# Metlino_QUAD_BUCK.net
KiCad netlist of a schematic drawn in Altium Designer
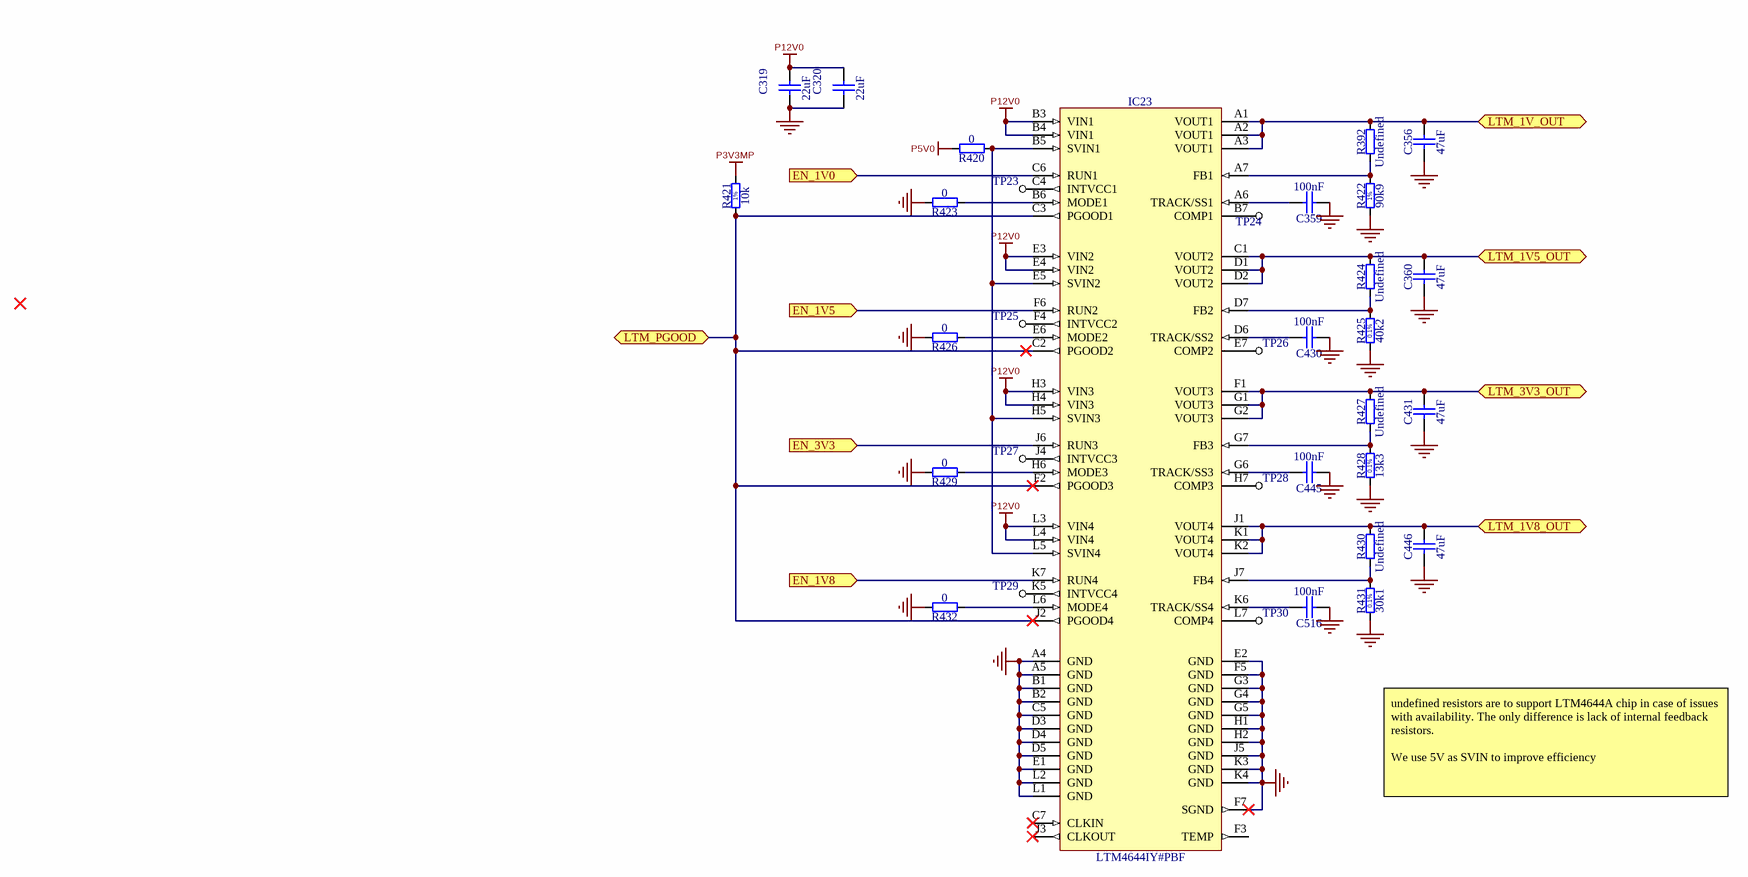
[diagram p0: Metlino_QUAD_BUCK.SchDoc]

(export (version "E")
  (design (tool "Eeschema 10.0.6"))
  (components
    (comp (ref "C319")
      (value "22uF")
      (footprint "CAPC2012X135N")
      (description "Non-polarised capacitor")
      (fields
        (field (name "MANUFACTURER PART NUMBER") "CC0805_22UF_16V_10%_X5R")
        (field (name "MANUFACTURER") "GENERIC")
        (field (name "AUTHOR") "CERN DEM JLC")
      )
      (libsource (lib "Capacitors") (part "Capacitor - non polarized"))
    )
    (comp (ref "C320")
      (value "22uF")
      (footprint "CAPC2012X135N")
      (description "Non-polarised capacitor")
      (fields
        (field (name "MANUFACTURER PART NUMBER") "CC0805_22UF_16V_10%_X5R")
        (field (name "MANUFACTURER") "GENERIC")
        (field (name "AUTHOR") "CERN DEM JLC")
      )
      (libsource (lib "Capacitors") (part "Capacitor - non polarized"))
    )
    (comp (ref "C356")
      (value "47uF")
      (footprint "CAPC2012X140N")
      (description "Non-polarised capacitor")
      (fields
        (field (name "MANUFACTURER PART NUMBER") "CC0805_47UF_6.3V_20%_X5R")
        (field (name "MANUFACTURER") "GENERIC")
        (field (name "AUTHOR") "CERN DEM JLC")
      )
      (libsource (lib "Capacitors") (part "Capacitor - non polarized"))
    )
    (comp (ref "C359")
      (value "100nF")
      (footprint "CAPC1005X55N")
      (description "Non-polarised capacitor")
      (fields
        (field (name "PART NUMBER") "CC0402_100NF_16V_10%_X5R")
        (field (name "VOLTAGE") "16V")
        (field (name "AUTHOR") "CERN DEM JLC")
      )
      (libsource (lib "Capacitors") (part "Capacitor - non polarized"))
    )
    (comp (ref "C360")
      (value "47uF")
      (footprint "CAPC2012X140N")
      (description "Non-polarised capacitor")
      (fields
        (field (name "MANUFACTURER PART NUMBER") "CC0805_47UF_6.3V_20%_X5R")
        (field (name "MANUFACTURER") "GENERIC")
        (field (name "AUTHOR") "CERN DEM JLC")
      )
      (libsource (lib "Capacitors") (part "Capacitor - non polarized"))
    )
    (comp (ref "C430")
      (value "100nF")
      (footprint "CAPC1005X55N")
      (description "Non-polarised capacitor")
      (fields
        (field (name "PART NUMBER") "CC0402_100NF_16V_10%_X5R")
        (field (name "VOLTAGE") "16V")
        (field (name "AUTHOR") "CERN DEM JLC")
      )
      (libsource (lib "Capacitors") (part "Capacitor - non polarized"))
    )
    (comp (ref "C431")
      (value "47uF")
      (footprint "CAPC2012X140N")
      (description "Non-polarised capacitor")
      (fields
        (field (name "MANUFACTURER PART NUMBER") "CC0805_47UF_6.3V_20%_X5R")
        (field (name "MANUFACTURER") "GENERIC")
        (field (name "AUTHOR") "CERN DEM JLC")
      )
      (libsource (lib "Capacitors") (part "Capacitor - non polarized"))
    )
    (comp (ref "C445")
      (value "100nF")
      (footprint "CAPC1005X55N")
      (description "Non-polarised capacitor")
      (fields
        (field (name "PART NUMBER") "CC0402_100NF_16V_10%_X5R")
        (field (name "VOLTAGE") "16V")
        (field (name "AUTHOR") "CERN DEM JLC")
      )
      (libsource (lib "Capacitors") (part "Capacitor - non polarized"))
    )
    (comp (ref "C446")
      (value "47uF")
      (footprint "CAPC2012X140N")
      (description "Non-polarised capacitor")
      (fields
        (field (name "MANUFACTURER PART NUMBER") "CC0805_47UF_6.3V_20%_X5R")
        (field (name "MANUFACTURER") "GENERIC")
        (field (name "AUTHOR") "CERN DEM JLC")
      )
      (libsource (lib "Capacitors") (part "Capacitor - non polarized"))
    )
    (comp (ref "C516")
      (value "100nF")
      (footprint "CAPC1005X55N")
      (description "Non-polarised capacitor")
      (fields
        (field (name "PART NUMBER") "CC0402_100NF_16V_10%_X5R")
        (field (name "VOLTAGE") "16V")
        (field (name "AUTHOR") "CERN DEM JLC")
      )
      (libsource (lib "Capacitors") (part "Capacitor - non polarized"))
    )
    (comp (ref "IC23")
      (value "LTM4644IY#PBF")
      (footprint "BGA77C127P7X11_900X1500X521")
      (description "Quad DC/DC µModule Regulator with Configurable 4A Output Array")
      (fields (field (name "MANUFACTURER") "LINEAR TECHNOLOGY") (field (name "AUTHOR") "CERN DEM JLC"))
      (libsource (lib "ICs And Semiconductors") (part "LTM4644"))
    )
    (comp (ref "R392")
      (value "Undefined")
      (footprint "RESC1608X55N")
      (description "Resistor")
      (fields (field (name "PART NUMBER") "R0603_NO-VALUE") (field (name "AUTHOR") "CERN DEM JLC"))
      (libsource (lib "Resistors") (part "Resistor"))
    )
    (comp (ref "R420")
      (value "0")
      (footprint "RESC1005X40N")
      (description "Resistor")
      (fields
        (field (name "MANUFACTURER PART NUMBER") "R0402_0R_JUMPER")
        (field (name "MANUFACTURER") "GENERIC")
        (field (name "AUTHOR") "CERN DEM JLC")
      )
      (libsource (lib "Resistors") (part "Resistor"))
    )
    (comp (ref "R421")
      (value "10k")
      (footprint "RESC1005X40N")
      (description "Resistor - 1%")
      (fields
        (field (name "MANUFACTURER PART NUMBER") "R0402_10K_1%_0.0625W_100PPM")
        (field (name "MANUFACTURER") "GENERIC")
        (field (name "AUTHOR") "CERN DEM JLC")
      )
      (libsource (lib "Resistors") (part "Resistor - 1%"))
    )
    (comp (ref "R422")
      (value "90k9")
      (footprint "RESC1608X55N")
      (description "Resistor - 1%")
      (fields
        (field (name "PART NUMBER") "R0603_90K9_1%_0.1W_100PPM")
        (field (name "POWER") "0.1W")
        (field (name "AUTHOR") "CERN DEM JLC")
      )
      (libsource (lib "Resistors") (part "Resistor - 1%"))
    )
    (comp (ref "R423")
      (value "0")
      (footprint "RESC1005X40N")
      (description "Resistor")
      (fields
        (field (name "MANUFACTURER PART NUMBER") "R0402_0R_JUMPER")
        (field (name "MANUFACTURER") "GENERIC")
        (field (name "AUTHOR") "CERN DEM JLC")
      )
      (libsource (lib "Resistors") (part "Resistor"))
    )
    (comp (ref "R424")
      (value "Undefined")
      (footprint "RESC1608X55N")
      (description "Resistor")
      (fields (field (name "PART NUMBER") "R0603_NO-VALUE") (field (name "AUTHOR") "CERN DEM JLC"))
      (libsource (lib "Resistors") (part "Resistor"))
    )
    (comp (ref "R425")
      (value "40k2")
      (footprint "RESC1608X55N")
      (description "Resistor - 0.1%")
      (fields
        (field (name "PART NUMBER") "R0603_40K2_0.1%_0.063W_10PPM")
        (field (name "POWER") "0.063W")
        (field (name "AUTHOR") "CERN DEM JLC")
      )
      (libsource (lib "Resistors") (part "Resistor - 0.1%"))
    )
    (comp (ref "R426")
      (value "0")
      (footprint "RESC1005X40N")
      (description "Resistor")
      (fields
        (field (name "MANUFACTURER PART NUMBER") "R0402_0R_JUMPER")
        (field (name "MANUFACTURER") "GENERIC")
        (field (name "AUTHOR") "CERN DEM JLC")
      )
      (libsource (lib "Resistors") (part "Resistor"))
    )
    (comp (ref "R427")
      (value "Undefined")
      (footprint "RESC1608X55N")
      (description "Resistor")
      (fields (field (name "PART NUMBER") "R0603_NO-VALUE") (field (name "AUTHOR") "CERN DEM JLC"))
      (libsource (lib "Resistors") (part "Resistor"))
    )
    (comp (ref "R428")
      (value "13k3")
      (footprint "RESC1608X55N")
      (description "Resistor - 0.1%")
      (fields
        (field (name "PART NUMBER") "R0603_13K3_0.1%_0.063W_10PPM")
        (field (name "POWER") "0.063W")
        (field (name "AUTHOR") "CERN DEM JLC")
      )
      (libsource (lib "Resistors") (part "Resistor - 0.1%"))
    )
    (comp (ref "R429")
      (value "0")
      (footprint "RESC1005X40N")
      (description "Resistor")
      (fields
        (field (name "MANUFACTURER PART NUMBER") "R0402_0R_JUMPER")
        (field (name "MANUFACTURER") "GENERIC")
        (field (name "AUTHOR") "CERN DEM JLC")
      )
      (libsource (lib "Resistors") (part "Resistor"))
    )
    (comp (ref "R430")
      (value "Undefined")
      (footprint "RESC1608X55N")
      (description "Resistor")
      (fields (field (name "PART NUMBER") "R0603_NO-VALUE") (field (name "AUTHOR") "CERN DEM JLC"))
      (libsource (lib "Resistors") (part "Resistor"))
    )
    (comp (ref "R431")
      (value "30k1")
      (footprint "RESC1608X55N")
      (description "Resistor - 0.1%")
      (fields
        (field (name "PART NUMBER") "R0603_30K1_0.1%_0.063W_10PPM")
        (field (name "POWER") "0.063W")
        (field (name "AUTHOR") "CERN DEM JLC")
      )
      (libsource (lib "Resistors") (part "Resistor - 0.1%"))
    )
    (comp (ref "R432")
      (value "0")
      (footprint "RESC1005X40N")
      (description "Resistor")
      (fields
        (field (name "MANUFACTURER PART NUMBER") "R0402_0R_JUMPER")
        (field (name "MANUFACTURER") "GENERIC")
        (field (name "AUTHOR") "CERN DEM JLC")
      )
      (libsource (lib "Resistors") (part "Resistor"))
    )
    (comp (ref "TP23")
      (value "TP")
      (footprint "TP")
      (description "Testpoint")
      (libsource (lib "LIBRARY_SCH") (part "TP"))
    )
    (comp (ref "TP24")
      (value "TP")
      (footprint "TP")
      (description "Testpoint")
      (libsource (lib "LIBRARY_SCH") (part "TP"))
    )
    (comp (ref "TP25")
      (value "TP")
      (footprint "TP")
      (description "Testpoint")
      (libsource (lib "LIBRARY_SCH") (part "TP"))
    )
    (comp (ref "TP26")
      (value "TP")
      (footprint "TP")
      (description "Testpoint")
      (libsource (lib "LIBRARY_SCH") (part "TP"))
    )
    (comp (ref "TP27")
      (value "TP")
      (footprint "TP")
      (description "Testpoint")
      (libsource (lib "LIBRARY_SCH") (part "TP"))
    )
    (comp (ref "TP28")
      (value "TP")
      (footprint "TP")
      (description "Testpoint")
      (libsource (lib "LIBRARY_SCH") (part "TP"))
    )
    (comp (ref "TP29")
      (value "TP")
      (footprint "TP")
      (description "Testpoint")
      (libsource (lib "LIBRARY_SCH") (part "TP"))
    )
    (comp (ref "TP30")
      (value "TP")
      (footprint "TP")
      (description "Testpoint")
      (libsource (lib "LIBRARY_SCH") (part "TP"))
    )
  )
  (nets
    (net (code "1") (name "/EN_1V0") (class "Default")
      (node (ref "IC23") (pin "C6") (pinfunction "RUN1_C6") (pintype "input"))
    )
    (net (code "2") (name "/EN_1V5") (class "Default")
      (node (ref "IC23") (pin "F6") (pinfunction "RUN2_F6") (pintype "input"))
    )
    (net (code "3") (name "/EN_1V8") (class "Default")
      (node (ref "IC23") (pin "K7") (pinfunction "RUN4_K7") (pintype "input"))
    )
    (net (code "4") (name "/EN_3V3") (class "Default")
      (node (ref "IC23") (pin "J6") (pinfunction "RUN3_J6") (pintype "input"))
    )
    (net (code "5") (name "/LTM_1V5_OUT") (class "Default")
      (node (ref "C360") (pin "2") (pinfunction "2_2") (pintype "passive"))
      (node (ref "IC23") (pin "C1") (pinfunction "VOUT2_C1") (pintype "power_in"))
      (node (ref "IC23") (pin "D1") (pinfunction "VOUT2_D1") (pintype "power_in"))
      (node (ref "IC23") (pin "D2") (pinfunction "VOUT2_D2") (pintype "power_in"))
      (node (ref "R424") (pin "2") (pinfunction "2_2") (pintype "passive"))
    )
    (net (code "6") (name "/LTM_1V8_OUT") (class "Default")
      (node (ref "C446") (pin "2") (pinfunction "2_2") (pintype "passive"))
      (node (ref "IC23") (pin "J1") (pinfunction "VOUT4_J1") (pintype "power_in"))
      (node (ref "IC23") (pin "K1") (pinfunction "VOUT4_K1") (pintype "power_in"))
      (node (ref "IC23") (pin "K2") (pinfunction "VOUT4_K2") (pintype "power_in"))
      (node (ref "R430") (pin "2") (pinfunction "2_2") (pintype "passive"))
    )
    (net (code "7") (name "/LTM_1V_OUT") (class "Default")
      (node (ref "C356") (pin "2") (pinfunction "2_2") (pintype "passive"))
      (node (ref "IC23") (pin "A1") (pinfunction "VOUT1_A1") (pintype "power_in"))
      (node (ref "IC23") (pin "A2") (pinfunction "VOUT1_A2") (pintype "power_in"))
      (node (ref "IC23") (pin "A3") (pinfunction "VOUT1_A3") (pintype "power_in"))
      (node (ref "R392") (pin "2") (pinfunction "2_2") (pintype "passive"))
    )
    (net (code "8") (name "/LTM_3V3_OUT") (class "Default")
      (node (ref "C431") (pin "2") (pinfunction "2_2") (pintype "passive"))
      (node (ref "IC23") (pin "F1") (pinfunction "VOUT3_F1") (pintype "power_in"))
      (node (ref "IC23") (pin "G1") (pinfunction "VOUT3_G1") (pintype "power_in"))
      (node (ref "IC23") (pin "G2") (pinfunction "VOUT3_G2") (pintype "power_in"))
      (node (ref "R427") (pin "2") (pinfunction "2_2") (pintype "passive"))
    )
    (net (code "9") (name "/LTM_PGOOD") (class "Default")
      (node (ref "IC23") (pin "C2") (pinfunction "PGOOD2_C2") (pintype "output"))
      (node (ref "IC23") (pin "C3") (pinfunction "PGOOD1_C3") (pintype "output"))
      (node (ref "IC23") (pin "F2") (pinfunction "PGOOD3_F2") (pintype "output"))
      (node (ref "IC23") (pin "J2") (pinfunction "PGOOD4_J2") (pintype "output"))
      (node (ref "R421") (pin "1") (pinfunction "1_1") (pintype "passive"))
    )
    (net (code "10") (name "GND") (class "Default")
      (node (ref "C319") (pin "1") (pinfunction "1_1") (pintype "passive"))
      (node (ref "C320") (pin "1") (pinfunction "1_1") (pintype "passive"))
      (node (ref "C356") (pin "1") (pinfunction "1_1") (pintype "passive"))
      (node (ref "C359") (pin "1") (pinfunction "1_1") (pintype "passive"))
      (node (ref "C360") (pin "1") (pinfunction "1_1") (pintype "passive"))
      (node (ref "C430") (pin "1") (pinfunction "1_1") (pintype "passive"))
      (node (ref "C431") (pin "1") (pinfunction "1_1") (pintype "passive"))
      (node (ref "C445") (pin "1") (pinfunction "1_1") (pintype "passive"))
      (node (ref "C446") (pin "1") (pinfunction "1_1") (pintype "passive"))
      (node (ref "C516") (pin "1") (pinfunction "1_1") (pintype "passive"))
      (node (ref "IC23") (pin "A4") (pinfunction "GND_A4") (pintype "power_in"))
      (node (ref "IC23") (pin "A5") (pinfunction "GND_A5") (pintype "power_in"))
      (node (ref "IC23") (pin "B1") (pinfunction "GND_B1") (pintype "power_in"))
      (node (ref "IC23") (pin "B2") (pinfunction "GND_B2") (pintype "power_in"))
      (node (ref "IC23") (pin "C5") (pinfunction "GND_C5") (pintype "power_in"))
      (node (ref "IC23") (pin "D3") (pinfunction "GND_D3") (pintype "power_in"))
      (node (ref "IC23") (pin "D4") (pinfunction "GND_D4") (pintype "power_in"))
      (node (ref "IC23") (pin "D5") (pinfunction "GND_D5") (pintype "power_in"))
      (node (ref "IC23") (pin "E1") (pinfunction "GND_E1") (pintype "power_in"))
      (node (ref "IC23") (pin "E2") (pinfunction "GND_E2") (pintype "power_in"))
      (node (ref "IC23") (pin "F5") (pinfunction "GND_F5") (pintype "power_in"))
      (node (ref "IC23") (pin "F7") (pinfunction "SGND_F7") (pintype "output"))
      (node (ref "IC23") (pin "G3") (pinfunction "GND_G3") (pintype "power_in"))
      (node (ref "IC23") (pin "G4") (pinfunction "GND_G4") (pintype "power_in"))
      (node (ref "IC23") (pin "G5") (pinfunction "GND_G5") (pintype "power_in"))
      (node (ref "IC23") (pin "H1") (pinfunction "GND_H1") (pintype "power_in"))
      (node (ref "IC23") (pin "H2") (pinfunction "GND_H2") (pintype "power_in"))
      (node (ref "IC23") (pin "J5") (pinfunction "GND_J5") (pintype "power_in"))
      (node (ref "IC23") (pin "K3") (pinfunction "GND_K3") (pintype "power_in"))
      (node (ref "IC23") (pin "K4") (pinfunction "GND_K4") (pintype "power_in"))
      (node (ref "IC23") (pin "L1") (pinfunction "GND_L1") (pintype "power_in"))
      (node (ref "IC23") (pin "L2") (pinfunction "GND_L2") (pintype "power_in"))
      (node (ref "R422") (pin "1") (pinfunction "1_1") (pintype "passive"))
      (node (ref "R423") (pin "2") (pinfunction "2_2") (pintype "passive"))
      (node (ref "R425") (pin "1") (pinfunction "1_1") (pintype "passive"))
      (node (ref "R426") (pin "2") (pinfunction "2_2") (pintype "passive"))
      (node (ref "R428") (pin "1") (pinfunction "1_1") (pintype "passive"))
      (node (ref "R429") (pin "2") (pinfunction "2_2") (pintype "passive"))
      (node (ref "R431") (pin "1") (pinfunction "1_1") (pintype "passive"))
      (node (ref "R432") (pin "2") (pinfunction "2_2") (pintype "passive"))
    )
    (net (code "11") (name "Net-(IC23-COMP1)") (class "Default")
      (node (ref "IC23") (pin "B7") (pinfunction "COMP1_B7") (pintype "passive"))
      (node (ref "TP24") (pin "1") (pintype "passive"))
    )
    (net (code "12") (name "Net-(IC23-COMP2)") (class "Default")
      (node (ref "IC23") (pin "E7") (pinfunction "COMP2_E7") (pintype "passive"))
      (node (ref "TP26") (pin "1") (pintype "passive"))
    )
    (net (code "13") (name "Net-(IC23-COMP3)") (class "Default")
      (node (ref "IC23") (pin "H7") (pinfunction "COMP3_H7") (pintype "passive"))
      (node (ref "TP28") (pin "1") (pintype "passive"))
    )
    (net (code "14") (name "Net-(IC23-COMP4)") (class "Default")
      (node (ref "IC23") (pin "L7") (pinfunction "COMP4_L7") (pintype "passive"))
      (node (ref "TP30") (pin "1") (pintype "passive"))
    )
    (net (code "15") (name "Net-(IC23-FB1)") (class "Default")
      (node (ref "IC23") (pin "A7") (pinfunction "FB1_A7") (pintype "input"))
      (node (ref "R392") (pin "1") (pinfunction "1_1") (pintype "passive"))
      (node (ref "R422") (pin "2") (pinfunction "2_2") (pintype "passive"))
    )
    (net (code "16") (name "Net-(IC23-FB2)") (class "Default")
      (node (ref "IC23") (pin "D7") (pinfunction "FB2_D7") (pintype "input"))
      (node (ref "R424") (pin "1") (pinfunction "1_1") (pintype "passive"))
      (node (ref "R425") (pin "2") (pinfunction "2_2") (pintype "passive"))
    )
    (net (code "17") (name "Net-(IC23-FB3)") (class "Default")
      (node (ref "IC23") (pin "G7") (pinfunction "FB3_G7") (pintype "input"))
      (node (ref "R427") (pin "1") (pinfunction "1_1") (pintype "passive"))
      (node (ref "R428") (pin "2") (pinfunction "2_2") (pintype "passive"))
    )
    (net (code "18") (name "Net-(IC23-FB4)") (class "Default")
      (node (ref "IC23") (pin "J7") (pinfunction "FB4_J7") (pintype "input"))
      (node (ref "R430") (pin "1") (pinfunction "1_1") (pintype "passive"))
      (node (ref "R431") (pin "2") (pinfunction "2_2") (pintype "passive"))
    )
    (net (code "19") (name "Net-(IC23-INTVCC1)") (class "Default")
      (node (ref "IC23") (pin "C4") (pinfunction "INTVCC1_C4") (pintype "output"))
      (node (ref "TP23") (pin "1") (pintype "passive"))
    )
    (net (code "20") (name "Net-(IC23-INTVCC2)") (class "Default")
      (node (ref "IC23") (pin "F4") (pinfunction "INTVCC2_F4") (pintype "output"))
      (node (ref "TP25") (pin "1") (pintype "passive"))
    )
    (net (code "21") (name "Net-(IC23-INTVCC3)") (class "Default")
      (node (ref "IC23") (pin "J4") (pinfunction "INTVCC3_J4") (pintype "output"))
      (node (ref "TP27") (pin "1") (pintype "passive"))
    )
    (net (code "22") (name "Net-(IC23-INTVCC4)") (class "Default")
      (node (ref "IC23") (pin "K5") (pinfunction "INTVCC4_K5") (pintype "output"))
      (node (ref "TP29") (pin "1") (pintype "passive"))
    )
    (net (code "23") (name "Net-(IC23-MODE1)") (class "Default")
      (node (ref "IC23") (pin "B6") (pinfunction "MODE1_B6") (pintype "input"))
      (node (ref "R423") (pin "1") (pinfunction "1_1") (pintype "passive"))
    )
    (net (code "24") (name "Net-(IC23-MODE2)") (class "Default")
      (node (ref "IC23") (pin "E6") (pinfunction "MODE2_E6") (pintype "input"))
      (node (ref "R426") (pin "1") (pinfunction "1_1") (pintype "passive"))
    )
    (net (code "25") (name "Net-(IC23-MODE3)") (class "Default")
      (node (ref "IC23") (pin "H6") (pinfunction "MODE3_H6") (pintype "input"))
      (node (ref "R429") (pin "1") (pinfunction "1_1") (pintype "passive"))
    )
    (net (code "26") (name "Net-(IC23-MODE4)") (class "Default")
      (node (ref "IC23") (pin "L6") (pinfunction "MODE4_L6") (pintype "input"))
      (node (ref "R432") (pin "1") (pinfunction "1_1") (pintype "passive"))
    )
    (net (code "27") (name "Net-(IC23-SVIN1)") (class "Default")
      (node (ref "IC23") (pin "B5") (pinfunction "SVIN1_B5") (pintype "input"))
      (node (ref "IC23") (pin "E5") (pinfunction "SVIN2_E5") (pintype "input"))
      (node (ref "IC23") (pin "H5") (pinfunction "SVIN3_H5") (pintype "input"))
      (node (ref "IC23") (pin "L5") (pinfunction "SVIN4_L5") (pintype "input"))
      (node (ref "R420") (pin "1") (pinfunction "1_1") (pintype "passive"))
    )
    (net (code "28") (name "Net-(IC23-TRACK{slash}SS1)") (class "Default")
      (node (ref "C359") (pin "2") (pinfunction "2_2") (pintype "passive"))
      (node (ref "IC23") (pin "A6") (pinfunction "TRACK/SS1_A6") (pintype "input"))
    )
    (net (code "29") (name "Net-(IC23-TRACK{slash}SS2)") (class "Default")
      (node (ref "C430") (pin "2") (pinfunction "2_2") (pintype "passive"))
      (node (ref "IC23") (pin "D6") (pinfunction "TRACK/SS2_D6") (pintype "input"))
    )
    (net (code "30") (name "Net-(IC23-TRACK{slash}SS3)") (class "Default")
      (node (ref "C445") (pin "2") (pinfunction "2_2") (pintype "passive"))
      (node (ref "IC23") (pin "G6") (pinfunction "TRACK/SS3_G6") (pintype "input"))
    )
    (net (code "31") (name "Net-(IC23-TRACK{slash}SS4)") (class "Default")
      (node (ref "C516") (pin "2") (pinfunction "2_2") (pintype "passive"))
      (node (ref "IC23") (pin "K6") (pinfunction "TRACK/SS4_K6") (pintype "input"))
    )
    (net (code "32") (name "P3V3MP") (class "Default")
      (node (ref "R421") (pin "2") (pinfunction "2_2") (pintype "passive"))
    )
    (net (code "33") (name "P5V0") (class "Default")
      (node (ref "R420") (pin "2") (pinfunction "2_2") (pintype "passive"))
    )
    (net (code "34") (name "P12V0") (class "Default")
      (node (ref "C319") (pin "2") (pinfunction "2_2") (pintype "passive"))
      (node (ref "C320") (pin "2") (pinfunction "2_2") (pintype "passive"))
      (node (ref "IC23") (pin "B3") (pinfunction "VIN1_B3") (pintype "input"))
      (node (ref "IC23") (pin "B4") (pinfunction "VIN1_B4") (pintype "input"))
      (node (ref "IC23") (pin "E3") (pinfunction "VIN2_E3") (pintype "input"))
      (node (ref "IC23") (pin "E4") (pinfunction "VIN2_E4") (pintype "input"))
      (node (ref "IC23") (pin "H3") (pinfunction "VIN3_H3") (pintype "input"))
      (node (ref "IC23") (pin "H4") (pinfunction "VIN3_H4") (pintype "input"))
      (node (ref "IC23") (pin "L3") (pinfunction "VIN4_L3") (pintype "input"))
      (node (ref "IC23") (pin "L4") (pinfunction "VIN4_L4") (pintype "input"))
    )
    (net (code "35") (name "unconnected-(IC23-CLKIN-PadC7)") (class "Default")
      (node (ref "IC23") (pin "C7") (pinfunction "CLKIN_C7") (pintype "input+no_connect"))
    )
    (net (code "36") (name "unconnected-(IC23-CLKOUT-PadJ3)") (class "Default")
      (node (ref "IC23") (pin "J3") (pinfunction "CLKOUT_J3") (pintype "output+no_connect"))
    )
    (net (code "37") (name "unconnected-(IC23-TEMP-PadF3)") (class "Default")
      (node (ref "IC23") (pin "F3") (pinfunction "TEMP_F3") (pintype "output"))
    )
  )
)
